# ZOWI_Main_Board_Multiplexer.net
KiCad netlist of a schematic drawn in Altium Designer
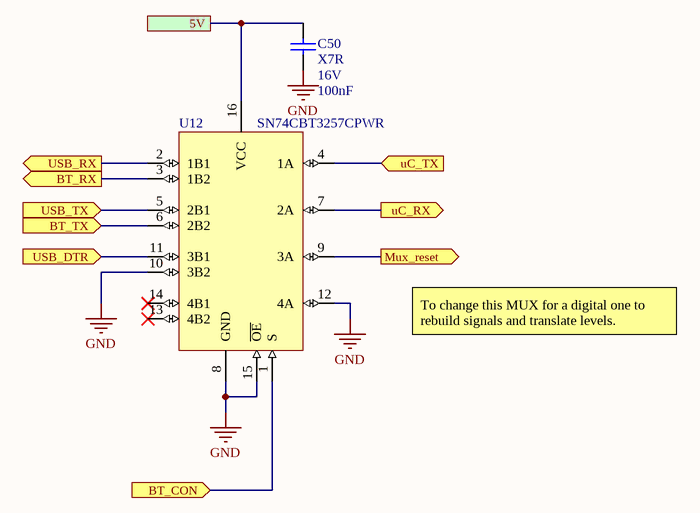
[diagram p0: ZOWI_Main_Board_Multiplexer.SchDoc]

(export (version "E")
  (design (tool "Eeschema 10.0.6"))
  (components
    (comp (ref "C50")
      (value "Capacitor")
      (footprint "C0402")
      (description "Capacitor SMD")
      (fields
        (field (name "DIELECTRIC") "X7R")
        (field (name "VOLTAGE") "16V")
        (field (name "CAPACITANCE") "100nF")
        (field (name "PART NUMBER") "C0402_100nF_16V_±10%")
        (field (name "TOLERANCE") "±10%")
      )
      (libsource (lib "Pasives_Capacitor_SMD") (part "Capacitor"))
    )
    (comp (ref "U12")
      (value "SN74CBT3257CPWR")
      (footprint "TSSOP16")
      (description "Multiplexer/demultiplexer Quad")
      (fields
        (field (name "PART NUMBER") "SN74CBT3257CP")
        (field (name "ORDERINGCODE") "SN74CBT3257CPWR")
        (field (name "MANUFACTURER") "Texas Instruments")
      )
      (libsource (lib "Semiconductors_Logic_Gate") (part "SN74CBT3257"))
    )
  )
  (nets
    (net (code "1") (name "/5V") (class "Default")
      (node (ref "C50") (pin "2") (pinfunction "2_2") (pintype "passive"))
      (node (ref "U12") (pin "16") (pinfunction "VCC_16") (pintype "power_in"))
    )
    (net (code "2") (name "/BT_CON") (class "Default")
      (node (ref "U12") (pin "1") (pinfunction "S_1") (pintype "input"))
    )
    (net (code "3") (name "/BT_RX") (class "Default")
      (node (ref "U12") (pin "3") (pinfunction "1B2_3") (pintype "bidirectional"))
    )
    (net (code "4") (name "/BT_TX") (class "Default")
      (node (ref "U12") (pin "6") (pinfunction "2B2_6") (pintype "bidirectional"))
    )
    (net (code "5") (name "/Mux_reset") (class "Default")
      (node (ref "U12") (pin "9") (pinfunction "3A_9") (pintype "bidirectional"))
    )
    (net (code "6") (name "/USB_DTR") (class "Default")
      (node (ref "U12") (pin "11") (pinfunction "3B1_11") (pintype "bidirectional"))
    )
    (net (code "7") (name "/USB_RX") (class "Default")
      (node (ref "U12") (pin "2") (pinfunction "1B1_2") (pintype "bidirectional"))
    )
    (net (code "8") (name "/USB_TX") (class "Default")
      (node (ref "U12") (pin "5") (pinfunction "2B1_5") (pintype "bidirectional"))
    )
    (net (code "9") (name "/uC_RX") (class "Default")
      (node (ref "U12") (pin "7") (pinfunction "2A_7") (pintype "bidirectional"))
    )
    (net (code "10") (name "/uC_TX") (class "Default")
      (node (ref "U12") (pin "4") (pinfunction "1A_4") (pintype "bidirectional"))
    )
    (net (code "11") (name "GND") (class "Default")
      (node (ref "C50") (pin "1") (pinfunction "1_1") (pintype "passive"))
      (node (ref "U12") (pin "10") (pinfunction "3B2_10") (pintype "bidirectional"))
      (node (ref "U12") (pin "12") (pinfunction "4A_12") (pintype "bidirectional"))
      (node (ref "U12") (pin "15") (pinfunction "~{OE}_15") (pintype "input"))
      (node (ref "U12") (pin "8") (pinfunction "GND_8") (pintype "power_in"))
    )
    (net (code "12") (name "unconnected-(U12-4B1-Pad14)") (class "Default")
      (node (ref "U12") (pin "14") (pinfunction "4B1_14") (pintype "bidirectional+no_connect"))
    )
    (net (code "13") (name "unconnected-(U12-4B2-Pad13)") (class "Default")
      (node (ref "U12") (pin "13") (pinfunction "4B2_13") (pintype "bidirectional+no_connect"))
    )
  )
)
